# 10MHzEOM.net
KiCad netlist of a schematic drawn in EasyEDA Pro
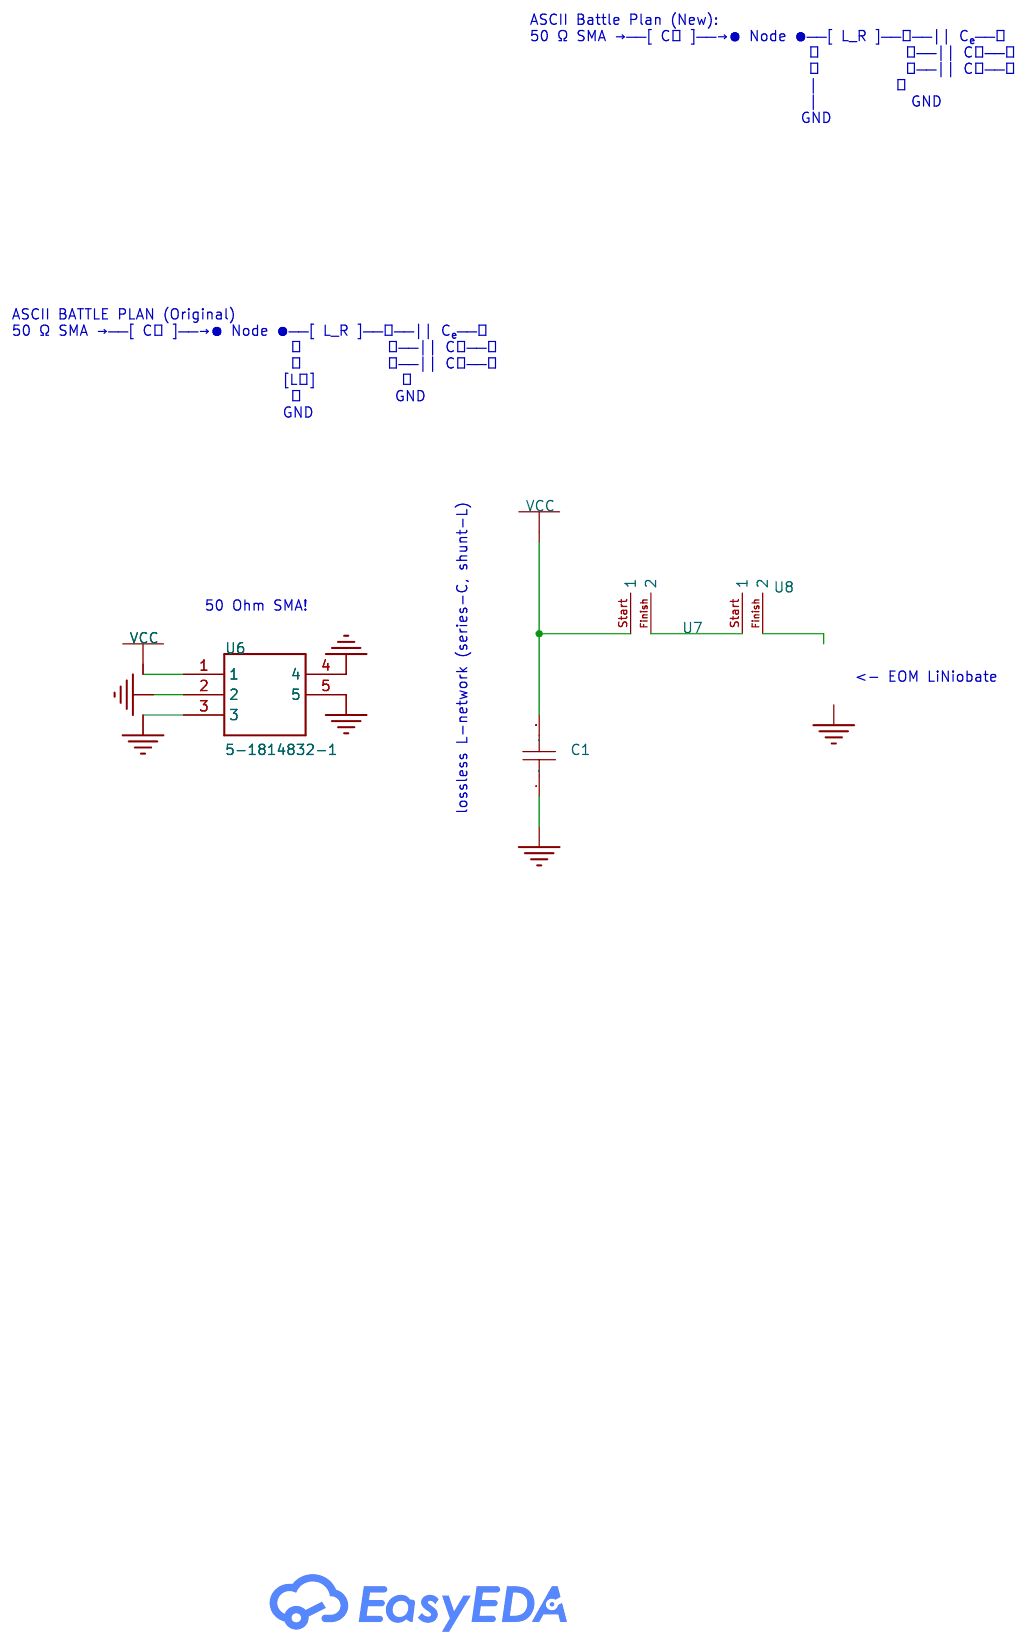
[diagram p0: schematic sheet]

(export (version "E")
  (design (tool "Eeschema 10.0.6"))
  (components
    (comp (ref "C1")
      (value "10nF")
      (footprint "easyedapro:C0805")
      (fields (field (name "Manufacturer Part") "0805B103K101NT") (field (name "Manufacturer") "FH(风华)"))
      (libsource (lib "easyedapro") (part "0805B103K101NT"))
    )
    (comp (ref "U6")
      (value "5-1814832-1")
      (footprint "easyedapro:5-1814832-1")
      (description "TSW-115-08-G-D-RA")
      (libsource (lib "easyedapro") (part "5-1814832-1"))
    )
    (comp (ref "U7")
      (value "~")
      (footprint "easyedapro:146-08J08L Adjustable")
      (libsource (lib "easyedapro") (part "146-08J08L Adjustable Inductor"))
    )
    (comp (ref "U8")
      (value "~")
      (footprint "easyedapro:1812CS-682")
      (description "1812CS-682")
      (libsource (lib "easyedapro") (part "1812CS-682"))
    )
  )
  (nets
    (net (code "1") (name "GND") (class "Default")
      (node (ref "C1") (pin "1") (pinfunction "1_1") (pintype "input"))
      (node (ref "U6") (pin "2") (pinfunction "2_2") (pintype "bidirectional"))
      (node (ref "U6") (pin "3") (pinfunction "3_3") (pintype "bidirectional"))
      (node (ref "U6") (pin "4") (pinfunction "4_4") (pintype "bidirectional"))
      (node (ref "U6") (pin "5") (pinfunction "5_5") (pintype "bidirectional"))
    )
    (net (code "2") (name "Net-(U7-2)") (class "Default")
      (node (ref "U7") (pin "Finish") (pinfunction "2_Finish") (pintype "input"))
      (node (ref "U8") (pin "Start") (pinfunction "1_Start") (pintype "input"))
    )
    (net (code "3") (name "VCC") (class "Default")
      (node (ref "C1") (pin "2") (pinfunction "2_2") (pintype "input"))
      (node (ref "U6") (pin "1") (pinfunction "1_1") (pintype "bidirectional"))
      (node (ref "U7") (pin "Start") (pinfunction "1_Start") (pintype "input"))
    )
    (net (code "4") (name "unconnected-(U8-2-PadFinish)") (class "Default")
      (node (ref "U8") (pin "Finish") (pinfunction "2_Finish") (pintype "input"))
    )
  )
)
